# Smart_energy_meter.net
KiCad netlist of a schematic drawn in Altium Designer
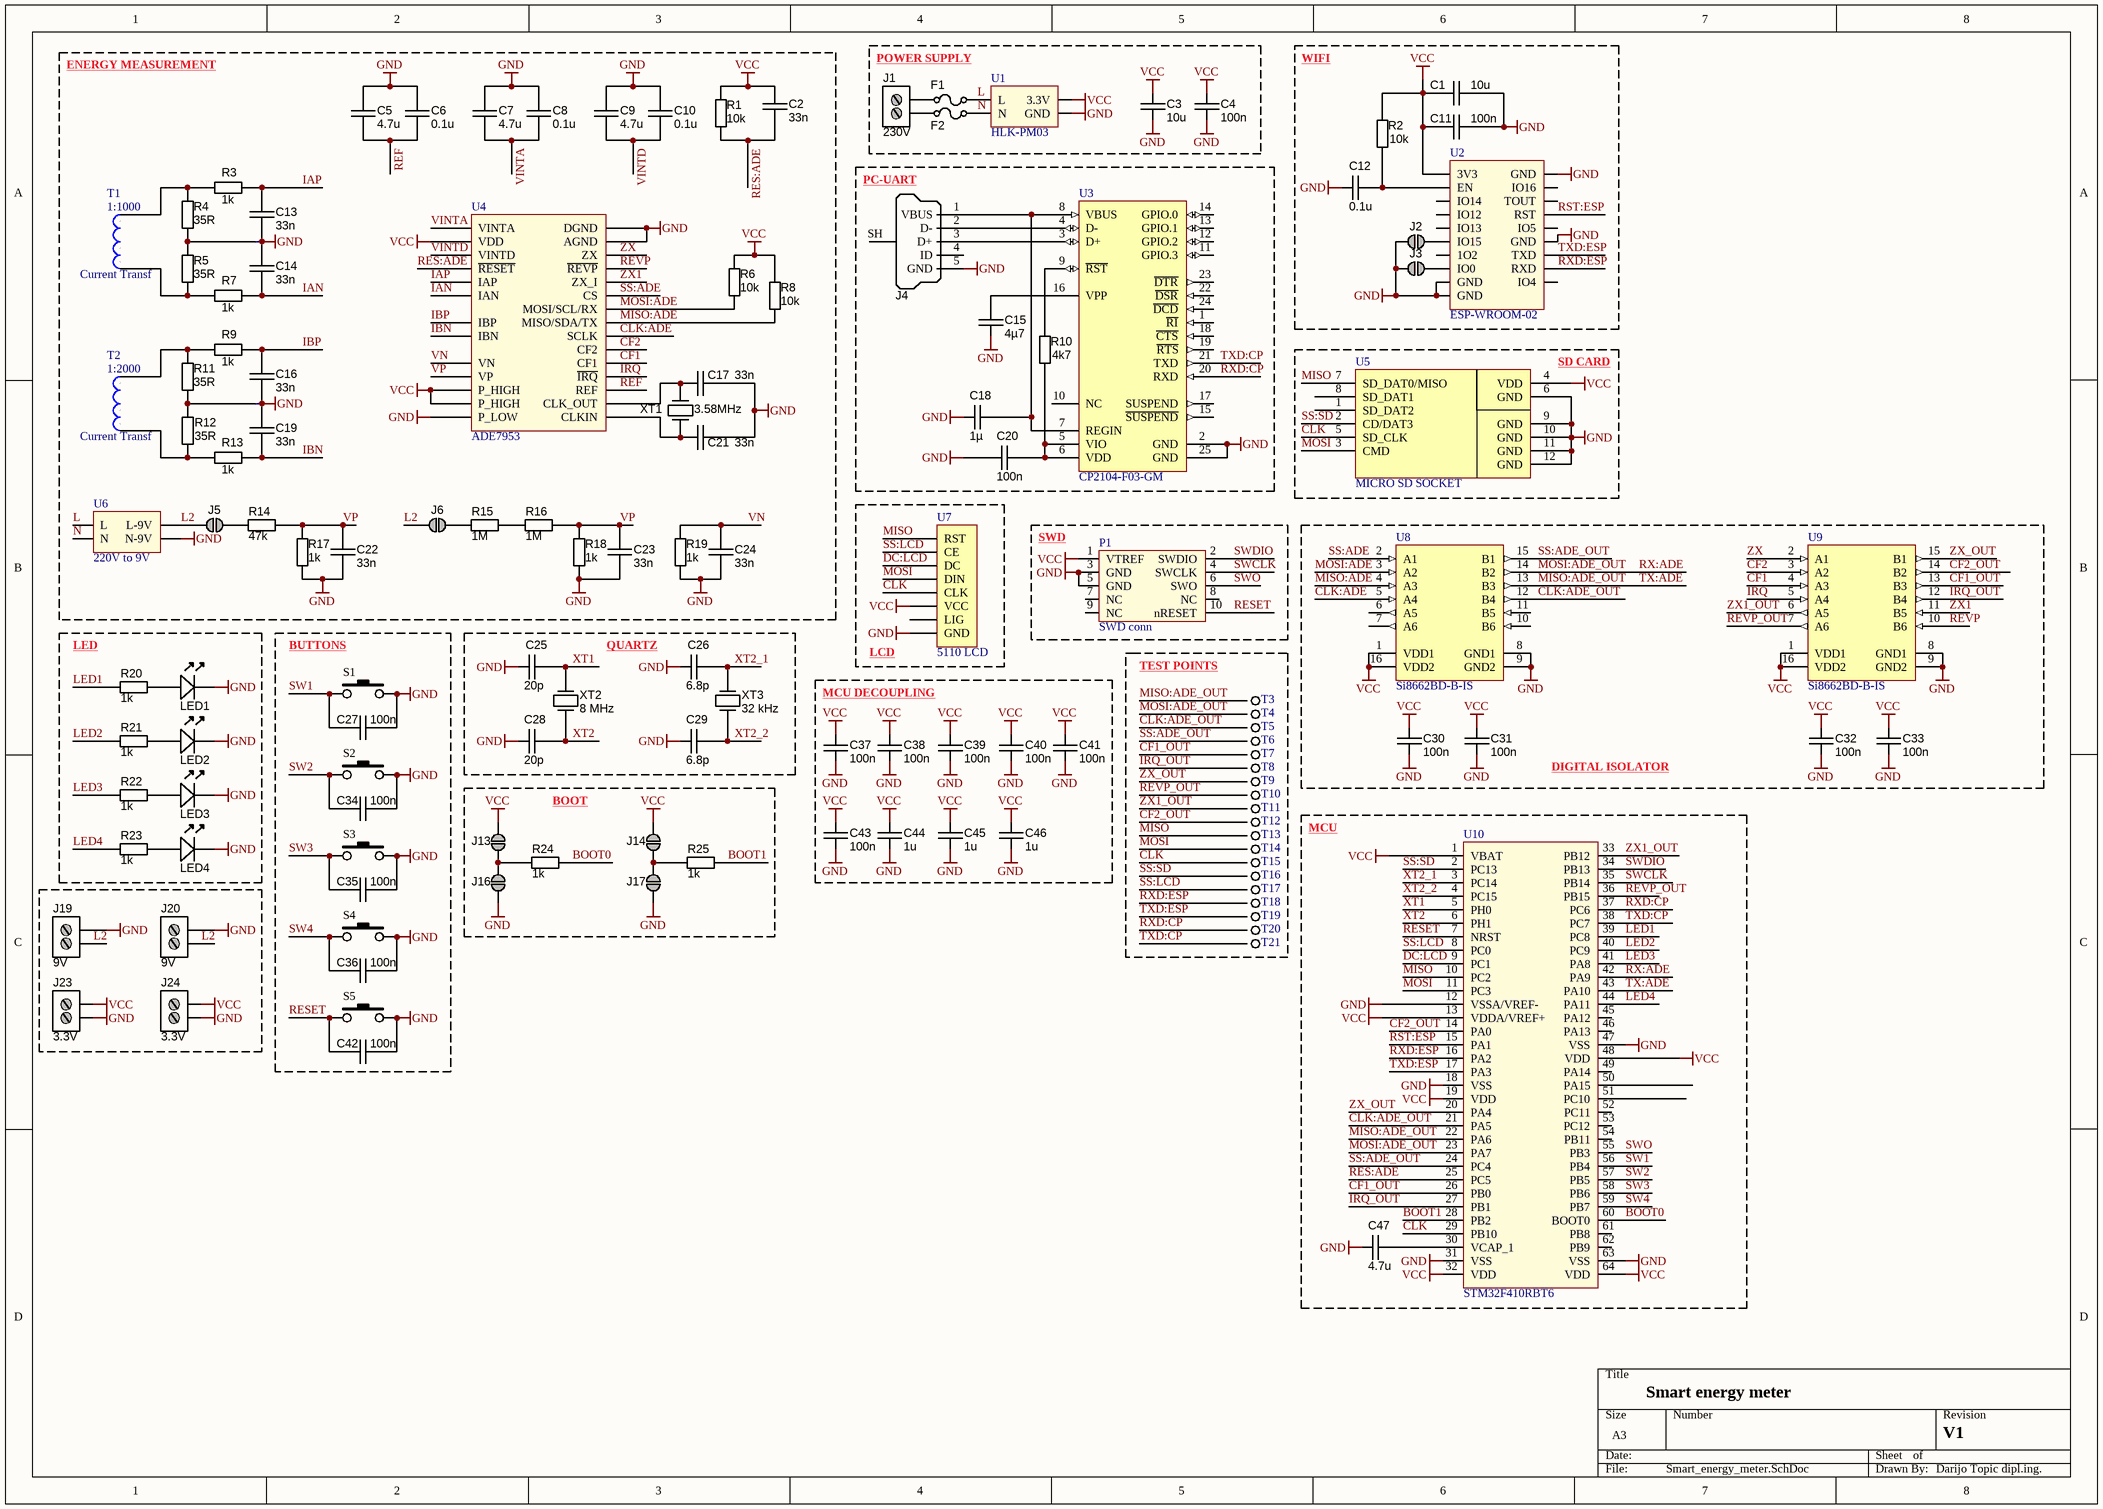
[diagram p0: Smart_energy_meter.SchDoc]

(export (version "E")
  (design (tool "Eeschema 10.0.6"))
  (components
    (comp (ref "C1")
      (value "10u")
      (footprint "CAPC2012X135N")
      (description "Capacitor SMD Cer 100nF 10% 50V X7R 0805")
      (fields (field (name "TOLERANCE") "±10%") (field (name "Comment") "approved sub OK"))
      (libsource (lib "PBL - Capacitors") (part "CAPC_100n_0805_X7R_50V_10%"))
    )
    (comp (ref "C2")
      (value "33n")
      (footprint "CAPC2012X135N")
      (description "Capacitor SMD Cer 100nF 10% 50V X7R 0805")
      (fields (field (name "TOLERANCE") "±10%") (field (name "Comment") "approved sub OK"))
      (libsource (lib "PBL - Capacitors") (part "CAPC_100n_0805_X7R_50V_10%"))
    )
    (comp (ref "C3")
      (value "10u")
      (footprint "CAPC2012X135N")
      (description "Capacitor SMD Cer 100nF 10% 50V X7R 0805")
      (fields (field (name "TOLERANCE") "±10%") (field (name "Comment") "approved sub OK"))
      (libsource (lib "PBL - Capacitors") (part "CAPC_100n_0805_X7R_50V_10%"))
    )
    (comp (ref "C4")
      (value "100n")
      (footprint "CAPC2012X135N")
      (description "Capacitor SMD Cer 100nF 10% 50V X7R 0805")
      (fields (field (name "TOLERANCE") "±10%") (field (name "Comment") "approved sub OK"))
      (libsource (lib "PBL - Capacitors") (part "CAPC_100n_0805_X7R_50V_10%"))
    )
    (comp (ref "C5")
      (value "4.7u")
      (footprint "CAPC2012X135N")
      (description "Capacitor SMD Cer 100nF 10% 50V X7R 0805")
      (fields (field (name "TOLERANCE") "±10%") (field (name "Comment") "approved sub OK"))
      (libsource (lib "PBL - Capacitors") (part "CAPC_100n_0805_X7R_50V_10%"))
    )
    (comp (ref "C6")
      (value "0.1u")
      (footprint "CAPC2012X135N")
      (description "Capacitor SMD Cer 100nF 10% 50V X7R 0805")
      (fields (field (name "TOLERANCE") "±10%") (field (name "Comment") "approved sub OK"))
      (libsource (lib "PBL - Capacitors") (part "CAPC_100n_0805_X7R_50V_10%"))
    )
    (comp (ref "C7")
      (value "4.7u")
      (footprint "CAPC2012X135N")
      (description "Capacitor SMD Cer 100nF 10% 50V X7R 0805")
      (fields (field (name "TOLERANCE") "±10%") (field (name "Comment") "approved sub OK"))
      (libsource (lib "PBL - Capacitors") (part "CAPC_100n_0805_X7R_50V_10%"))
    )
    (comp (ref "C8")
      (value "0.1u")
      (footprint "CAPC2012X135N")
      (description "Capacitor SMD Cer 100nF 10% 50V X7R 0805")
      (fields (field (name "TOLERANCE") "±10%") (field (name "Comment") "approved sub OK"))
      (libsource (lib "PBL - Capacitors") (part "CAPC_100n_0805_X7R_50V_10%"))
    )
    (comp (ref "C9")
      (value "4.7u")
      (footprint "CAPC2012X135N")
      (description "Capacitor SMD Cer 100nF 10% 50V X7R 0805")
      (fields (field (name "TOLERANCE") "±10%") (field (name "Comment") "approved sub OK"))
      (libsource (lib "PBL - Capacitors") (part "CAPC_100n_0805_X7R_50V_10%"))
    )
    (comp (ref "C10")
      (value "0.1u")
      (footprint "CAPC2012X135N")
      (description "Capacitor SMD Cer 100nF 10% 50V X7R 0805")
      (fields (field (name "TOLERANCE") "±10%") (field (name "Comment") "approved sub OK"))
      (libsource (lib "PBL - Capacitors") (part "CAPC_100n_0805_X7R_50V_10%"))
    )
    (comp (ref "C11")
      (value "100n")
      (footprint "CAPC2012X135N")
      (description "Capacitor SMD Cer 100nF 10% 50V X7R 0805")
      (fields (field (name "TOLERANCE") "±10%") (field (name "Comment") "approved sub OK"))
      (libsource (lib "PBL - Capacitors") (part "CAPC_100n_0805_X7R_50V_10%"))
    )
    (comp (ref "C12")
      (value "0.1u")
      (footprint "CAPC2012X135N")
      (description "Capacitor SMD Cer 100nF 10% 50V X7R 0805")
      (fields (field (name "TOLERANCE") "±10%") (field (name "Comment") "approved sub OK"))
      (libsource (lib "PBL - Capacitors") (part "CAPC_100n_0805_X7R_50V_10%"))
    )
    (comp (ref "C13")
      (value "33n")
      (footprint "CAPC2012X135N")
      (description "Capacitor SMD Cer 100nF 10% 50V X7R 0805")
      (fields (field (name "TOLERANCE") "±10%") (field (name "Comment") "approved sub OK"))
      (libsource (lib "PBL - Capacitors") (part "CAPC_100n_0805_X7R_50V_10%"))
    )
    (comp (ref "C14")
      (value "33n")
      (footprint "CAPC2012X135N")
      (description "Capacitor SMD Cer 100nF 10% 50V X7R 0805")
      (fields (field (name "TOLERANCE") "±10%") (field (name "Comment") "approved sub OK"))
      (libsource (lib "PBL - Capacitors") (part "CAPC_100n_0805_X7R_50V_10%"))
    )
    (comp (ref "C15")
      (value "4µ7")
      (footprint "CAPC2012X135N")
      (description "Capacitor SMD Cer 4.7uF 10% 16V X5R 0805")
      (fields (field (name "TOLERANCE") "±10%") (field (name "Comment") "approved sub OK"))
      (libsource (lib "PBL - Capacitors") (part "CAPC_4u7_0805"))
    )
    (comp (ref "C16")
      (value "33n")
      (footprint "CAPC2012X135N")
      (description "Capacitor SMD Cer 100nF 10% 50V X7R 0805")
      (fields (field (name "TOLERANCE") "±10%") (field (name "Comment") "approved sub OK"))
      (libsource (lib "PBL - Capacitors") (part "CAPC_100n_0805_X7R_50V_10%"))
    )
    (comp (ref "C17")
      (value "33n")
      (footprint "CAPC2012X135N")
      (description "Capacitor SMD Cer 100nF 10% 50V X7R 0805")
      (fields (field (name "TOLERANCE") "±10%") (field (name "Comment") "approved sub OK"))
      (libsource (lib "PBL - Capacitors") (part "CAPC_100n_0805_X7R_50V_10%"))
    )
    (comp (ref "C18")
      (value "1µ")
      (footprint "CAPC2012X135N")
      (description "Capacitor SMD Cer 1uF 10% 16V X7R 0805")
      (fields (field (name "TOLERANCE") "±10%") (field (name "Comment") "approved sub OK"))
      (libsource (lib "PBL - Capacitors") (part "CAPC_1u_0805_X7R_16V_10%"))
    )
    (comp (ref "C19")
      (value "33n")
      (footprint "CAPC2012X135N")
      (description "Capacitor SMD Cer 100nF 10% 50V X7R 0805")
      (fields (field (name "TOLERANCE") "±10%") (field (name "Comment") "approved sub OK"))
      (libsource (lib "PBL - Capacitors") (part "CAPC_100n_0805_X7R_50V_10%"))
    )
    (comp (ref "C20")
      (value "100n")
      (footprint "CAPC2012X135N")
      (description "Capacitor SMD Cer 100nF 10% 50V X7R 0805")
      (fields (field (name "TOLERANCE") "±10%") (field (name "Comment") "approved sub OK"))
      (libsource (lib "PBL - Capacitors") (part "CAPC_100n_0805_X7R_50V_10%"))
    )
    (comp (ref "C21")
      (value "33n")
      (footprint "CAPC2012X135N")
      (description "Capacitor SMD Cer 100nF 10% 50V X7R 0805")
      (fields (field (name "TOLERANCE") "±10%") (field (name "Comment") "approved sub OK"))
      (libsource (lib "PBL - Capacitors") (part "CAPC_100n_0805_X7R_50V_10%"))
    )
    (comp (ref "C22")
      (value "33n")
      (footprint "CAPC2012X135N")
      (description "Capacitor SMD Cer 100nF 10% 50V X7R 0805")
      (fields (field (name "TOLERANCE") "±10%") (field (name "Comment") "approved sub OK"))
      (libsource (lib "PBL - Capacitors") (part "CAPC_100n_0805_X7R_50V_10%"))
    )
    (comp (ref "C23")
      (value "33n")
      (footprint "CAPC2012X135N")
      (description "Capacitor SMD Cer 100nF 10% 50V X7R 0805")
      (fields (field (name "TOLERANCE") "±10%") (field (name "Comment") "approved sub OK"))
      (libsource (lib "PBL - Capacitors") (part "CAPC_100n_0805_X7R_50V_10%"))
    )
    (comp (ref "C24")
      (value "33n")
      (footprint "CAPC2012X135N")
      (description "Capacitor SMD Cer 100nF 10% 50V X7R 0805")
      (fields (field (name "TOLERANCE") "±10%") (field (name "Comment") "approved sub OK"))
      (libsource (lib "PBL - Capacitors") (part "CAPC_100n_0805_X7R_50V_10%"))
    )
    (comp (ref "C25")
      (value "20p")
      (footprint "CAPC2012X135N")
      (description "Capacitor SMD Cer 100nF 10% 50V X7R 0805")
      (fields (field (name "TOLERANCE") "±10%") (field (name "Comment") "approved sub OK"))
      (libsource (lib "PBL - Capacitors") (part "CAPC_100n_0805_X7R_50V_10%"))
    )
    (comp (ref "C26")
      (value "6.8p")
      (footprint "CAPC2012X135N")
      (description "Capacitor SMD Cer 100nF 10% 50V X7R 0805")
      (fields (field (name "TOLERANCE") "±10%") (field (name "Comment") "approved sub OK"))
      (libsource (lib "PBL - Capacitors") (part "CAPC_100n_0805_X7R_50V_10%"))
    )
    (comp (ref "C27")
      (value "100n")
      (footprint "CAPC2012X135N")
      (description "Capacitor SMD Cer 100nF 10% 50V X7R 0805")
      (fields (field (name "TOLERANCE") "±10%") (field (name "Comment") "approved sub OK"))
      (libsource (lib "PBL - Capacitors") (part "CAPC_100n_0805_X7R_50V_10%"))
    )
    (comp (ref "C28")
      (value "20p")
      (footprint "CAPC2012X135N")
      (description "Capacitor SMD Cer 100nF 10% 50V X7R 0805")
      (fields (field (name "TOLERANCE") "±10%") (field (name "Comment") "approved sub OK"))
      (libsource (lib "PBL - Capacitors") (part "CAPC_100n_0805_X7R_50V_10%"))
    )
    (comp (ref "C29")
      (value "6.8p")
      (footprint "CAPC2012X135N")
      (description "Capacitor SMD Cer 100nF 10% 50V X7R 0805")
      (fields (field (name "TOLERANCE") "±10%") (field (name "Comment") "approved sub OK"))
      (libsource (lib "PBL - Capacitors") (part "CAPC_100n_0805_X7R_50V_10%"))
    )
    (comp (ref "C30")
      (value "100n")
      (footprint "CAPC2012X135N")
      (description "Capacitor SMD Cer 100nF 10% 50V X7R 0805")
      (fields (field (name "TOLERANCE") "±10%") (field (name "Comment") "approved sub OK"))
      (libsource (lib "PBL - Capacitors") (part "CAPC_100n_0805_X7R_50V_10%"))
    )
    (comp (ref "C31")
      (value "100n")
      (footprint "CAPC2012X135N")
      (description "Capacitor SMD Cer 100nF 10% 50V X7R 0805")
      (fields (field (name "TOLERANCE") "±10%") (field (name "Comment") "approved sub OK"))
      (libsource (lib "PBL - Capacitors") (part "CAPC_100n_0805_X7R_50V_10%"))
    )
    (comp (ref "C32")
      (value "100n")
      (footprint "CAPC2012X135N")
      (description "Capacitor SMD Cer 100nF 10% 50V X7R 0805")
      (fields (field (name "TOLERANCE") "±10%") (field (name "Comment") "approved sub OK"))
      (libsource (lib "PBL - Capacitors") (part "CAPC_100n_0805_X7R_50V_10%"))
    )
    (comp (ref "C33")
      (value "100n")
      (footprint "CAPC2012X135N")
      (description "Capacitor SMD Cer 100nF 10% 50V X7R 0805")
      (fields (field (name "TOLERANCE") "±10%") (field (name "Comment") "approved sub OK"))
      (libsource (lib "PBL - Capacitors") (part "CAPC_100n_0805_X7R_50V_10%"))
    )
    (comp (ref "C34")
      (value "100n")
      (footprint "CAPC2012X135N")
      (description "Capacitor SMD Cer 100nF 10% 50V X7R 0805")
      (fields (field (name "TOLERANCE") "±10%") (field (name "Comment") "approved sub OK"))
      (libsource (lib "PBL - Capacitors") (part "CAPC_100n_0805_X7R_50V_10%"))
    )
    (comp (ref "C35")
      (value "100n")
      (footprint "CAPC2012X135N")
      (description "Capacitor SMD Cer 100nF 10% 50V X7R 0805")
      (fields (field (name "TOLERANCE") "±10%") (field (name "Comment") "approved sub OK"))
      (libsource (lib "PBL - Capacitors") (part "CAPC_100n_0805_X7R_50V_10%"))
    )
    (comp (ref "C36")
      (value "100n")
      (footprint "CAPC2012X135N")
      (description "Capacitor SMD Cer 100nF 10% 50V X7R 0805")
      (fields (field (name "TOLERANCE") "±10%") (field (name "Comment") "approved sub OK"))
      (libsource (lib "PBL - Capacitors") (part "CAPC_100n_0805_X7R_50V_10%"))
    )
    (comp (ref "C37")
      (value "100n")
      (footprint "CAPC2012X135N")
      (description "Capacitor SMD Cer 100nF 10% 50V X7R 0805")
      (fields (field (name "TOLERANCE") "±10%") (field (name "Comment") "approved sub OK"))
      (libsource (lib "PBL - Capacitors") (part "CAPC_100n_0805_X7R_50V_10%"))
    )
    (comp (ref "C38")
      (value "100n")
      (footprint "CAPC2012X135N")
      (description "Capacitor SMD Cer 100nF 10% 50V X7R 0805")
      (fields (field (name "TOLERANCE") "±10%") (field (name "Comment") "approved sub OK"))
      (libsource (lib "PBL - Capacitors") (part "CAPC_100n_0805_X7R_50V_10%"))
    )
    (comp (ref "C39")
      (value "100n")
      (footprint "CAPC2012X135N")
      (description "Capacitor SMD Cer 100nF 10% 50V X7R 0805")
      (fields (field (name "TOLERANCE") "±10%") (field (name "Comment") "approved sub OK"))
      (libsource (lib "PBL - Capacitors") (part "CAPC_100n_0805_X7R_50V_10%"))
    )
    (comp (ref "C40")
      (value "100n")
      (footprint "CAPC2012X135N")
      (description "Capacitor SMD Cer 100nF 10% 50V X7R 0805")
      (fields (field (name "TOLERANCE") "±10%") (field (name "Comment") "approved sub OK"))
      (libsource (lib "PBL - Capacitors") (part "CAPC_100n_0805_X7R_50V_10%"))
    )
    (comp (ref "C41")
      (value "100n")
      (footprint "CAPC2012X135N")
      (description "Capacitor SMD Cer 100nF 10% 50V X7R 0805")
      (fields (field (name "TOLERANCE") "±10%") (field (name "Comment") "approved sub OK"))
      (libsource (lib "PBL - Capacitors") (part "CAPC_100n_0805_X7R_50V_10%"))
    )
    (comp (ref "C42")
      (value "100n")
      (footprint "CAPC2012X135N")
      (description "Capacitor SMD Cer 100nF 10% 50V X7R 0805")
      (fields (field (name "TOLERANCE") "±10%") (field (name "Comment") "approved sub OK"))
      (libsource (lib "PBL - Capacitors") (part "CAPC_100n_0805_X7R_50V_10%"))
    )
    (comp (ref "C43")
      (value "100n")
      (footprint "CAPC2012X135N")
      (description "Capacitor SMD Cer 100nF 10% 50V X7R 0805")
      (fields (field (name "TOLERANCE") "±10%") (field (name "Comment") "approved sub OK"))
      (libsource (lib "PBL - Capacitors") (part "CAPC_100n_0805_X7R_50V_10%"))
    )
    (comp (ref "C44")
      (value "1u")
      (footprint "CAPC2012X135N")
      (description "Capacitor SMD Cer 100nF 10% 50V X7R 0805")
      (fields (field (name "TOLERANCE") "±10%") (field (name "Comment") "approved sub OK"))
      (libsource (lib "PBL - Capacitors") (part "CAPC_100n_0805_X7R_50V_10%"))
    )
    (comp (ref "C45")
      (value "1u")
      (footprint "CAPC2012X135N")
      (description "Capacitor SMD Cer 100nF 10% 50V X7R 0805")
      (fields (field (name "TOLERANCE") "±10%") (field (name "Comment") "approved sub OK"))
      (libsource (lib "PBL - Capacitors") (part "CAPC_100n_0805_X7R_50V_10%"))
    )
    (comp (ref "C46")
      (value "1u")
      (footprint "CAPC2012X135N")
      (description "Capacitor SMD Cer 100nF 10% 50V X7R 0805")
      (fields (field (name "TOLERANCE") "±10%") (field (name "Comment") "approved sub OK"))
      (libsource (lib "PBL - Capacitors") (part "CAPC_100n_0805_X7R_50V_10%"))
    )
    (comp (ref "C47")
      (value "4.7u")
      (footprint "CAPC2012X135N")
      (description "Capacitor SMD Cer 100nF 10% 50V X7R 0805")
      (fields (field (name "TOLERANCE") "±10%") (field (name "Comment") "approved sub OK"))
      (libsource (lib "PBL - Capacitors") (part "CAPC_100n_0805_X7R_50V_10%"))
    )
    (comp (ref "F1")
      (value "Slow-blow")
      (footprint "Fuses 20A 250VAC")
      (description "Fuse 160mA 63VDC 0603 SMD")
      (libsource (lib "PBL - Fuses and Protection") (part "FUSE_160mA_0603"))
    )
    (comp (ref "F2")
      (value "Slow-blow")
      (footprint "Fuses 20A 250VAC")
      (description "Fuse 160mA 63VDC 0603 SMD")
      (libsource (lib "PBL - Fuses and Protection") (part "FUSE_160mA_0603"))
    )
    (comp (ref "J1")
      (value "230V")
      (footprint "2P_PCB_ScrewTerm_90S_3.81MM")
      (description "Terminal Block Screw Type THT 2-Position 3.81mm pitch")
      (libsource (lib "PBL - Connectors") (part "2P_ScrewTerm_90S_3.81MM"))
    )
    (comp (ref "J2")
      (value "Jumper")
      (footprint "HDR1X2")
      (description "SMD jumper")
      (libsource (lib "PBL - Pads and Jumpers") (part "JUMP1"))
    )
    (comp (ref "J3")
      (value "Jumper")
      (footprint "HDR1X2")
      (description "SMD jumper")
      (libsource (lib "PBL - Pads and Jumpers") (part "JUMP1"))
    )
    (comp (ref "J4")
      (value "USB Micro Type B (recommended if hand soldering)")
      (footprint "PBL - SMD Packages:USB_Micro-B_FCI_SMD")
      (description "Connector SMD-THD USB Micro Type B middle mount")
      (libsource (lib "PBL - Connectors") (part "USB_Micro_TypeB_FCI"))
    )
    (comp (ref "J5")
      (value "Jumper")
      (footprint "HDR1X2")
      (description "SMD jumper")
      (libsource (lib "PBL - Pads and Jumpers") (part "JUMP1"))
    )
    (comp (ref "J6")
      (value "Jumper")
      (footprint "HDR1X2")
      (description "SMD jumper")
      (libsource (lib "PBL - Pads and Jumpers") (part "JUMP1"))
    )
    (comp (ref "J13")
      (value "Jumper")
      (footprint "HDR1X2")
      (description "SMD jumper")
      (libsource (lib "PBL - Pads and Jumpers") (part "JUMP1"))
    )
    (comp (ref "J14")
      (value "Jumper")
      (footprint "HDR1X2")
      (description "SMD jumper")
      (libsource (lib "PBL - Pads and Jumpers") (part "JUMP1"))
    )
    (comp (ref "J16")
      (value "Jumper")
      (footprint "HDR1X2")
      (description "SMD jumper")
      (libsource (lib "PBL - Pads and Jumpers") (part "JUMP1"))
    )
    (comp (ref "J17")
      (value "Jumper")
      (footprint "HDR1X2")
      (description "SMD jumper")
      (libsource (lib "PBL - Pads and Jumpers") (part "JUMP1"))
    )
    (comp (ref "J19")
      (value "9V")
      (footprint "2P_PCB_ScrewTerm_90S_3.81MM")
      (description "Terminal Block Screw Type THT 2-Position 3.81mm pitch")
      (libsource (lib "PBL - Connectors") (part "2P_ScrewTerm_90S_3.81MM"))
    )
    (comp (ref "J20")
      (value "9V")
      (footprint "2P_PCB_ScrewTerm_90S_3.81MM")
      (description "Terminal Block Screw Type THT 2-Position 3.81mm pitch")
      (libsource (lib "PBL - Connectors") (part "2P_ScrewTerm_90S_3.81MM"))
    )
    (comp (ref "J23")
      (value "3.3V")
      (footprint "2P_PCB_ScrewTerm_90S_3.81MM")
      (description "Terminal Block Screw Type THT 2-Position 3.81mm pitch")
      (libsource (lib "PBL - Connectors") (part "2P_ScrewTerm_90S_3.81MM"))
    )
    (comp (ref "J24")
      (value "3.3V")
      (footprint "2P_PCB_ScrewTerm_90S_3.81MM")
      (description "Terminal Block Screw Type THT 2-Position 3.81mm pitch")
      (libsource (lib "PBL - Connectors") (part "2P_ScrewTerm_90S_3.81MM"))
    )
    (comp (ref "LED1")
      (value "~")
      (footprint "LED-0805-K")
      (description "LED, 0805 SMD, Green")
      (libsource (lib "PBL - Light Sources") (part "LED_SMD_Green_0805_6mcd"))
    )
    (comp (ref "LED2")
      (value "~")
      (footprint "LED-0805-K")
      (description "LED, 0805 SMD, Green")
      (libsource (lib "PBL - Light Sources") (part "LED_SMD_Green_0805_6mcd"))
    )
    (comp (ref "LED3")
      (value "~")
      (footprint "LED-0805-K")
      (description "LED, 0805 SMD, Green")
      (libsource (lib "PBL - Light Sources") (part "LED_SMD_Green_0805_6mcd"))
    )
    (comp (ref "LED4")
      (value "~")
      (footprint "LED-0805-K")
      (description "LED, 0805 SMD, Green")
      (libsource (lib "PBL - Light Sources") (part "LED_SMD_Green_0805_6mcd"))
    )
    (comp (ref "P1")
      (value "SWD conn")
      (footprint "HDR2X5_CEN")
      (description "SWD connector")
      (libsource (lib "Lib_darijo") (part "SW_debug"))
    )
    (comp (ref "R1")
      (value "10k")
      (footprint "RESC2012X70N")
      (description "Resistor SMD chip 4.7k Ohm 0.125W 1% 0805")
      (fields (field (name "TOLERANCE") "±1%") (field (name "Comment") "Thick Film"))
      (libsource (lib "PBL - Resistors") (part "RES_4K7_0805_1%"))
    )
    (comp (ref "R2")
      (value "10k")
      (footprint "RESC2012X70N")
      (description "Resistor SMD chip 4.7k Ohm 0.125W 1% 0805")
      (fields (field (name "TOLERANCE") "±1%") (field (name "Comment") "Thick Film"))
      (libsource (lib "") (part "RES_4K7_0805_1%_1"))
    )
    (comp (ref "R3")
      (value "1k")
      (footprint "RESC2012X70N")
      (description "Resistor SMD chip 4.7k Ohm 0.125W 1% 0805")
      (fields (field (name "TOLERANCE") "±1%") (field (name "Comment") "Thick Film"))
      (libsource (lib "") (part "RES_4K7_0805_1%_2"))
    )
    (comp (ref "R4")
      (value "35R")
      (footprint "RESC2012X70N")
      (description "Resistor SMD chip 4.7k Ohm 0.125W 1% 0805")
      (fields (field (name "TOLERANCE") "±1%") (field (name "Comment") "Thick Film"))
      (libsource (lib "PBL - Resistors") (part "RES_4K7_0805_1%"))
    )
    (comp (ref "R5")
      (value "35R")
      (footprint "RESC2012X70N")
      (description "Resistor SMD chip 4.7k Ohm 0.125W 1% 0805")
      (fields (field (name "TOLERANCE") "±1%") (field (name "Comment") "Thick Film"))
      (libsource (lib "PBL - Resistors") (part "RES_4K7_0805_1%"))
    )
    (comp (ref "R6")
      (value "10k")
      (footprint "RESC2012X70N")
      (description "Resistor SMD chip 4.7k Ohm 0.125W 1% 0805")
      (fields (field (name "TOLERANCE") "±1%") (field (name "Comment") "Thick Film"))
      (libsource (lib "PBL - Resistors") (part "RES_4K7_0805_1%"))
    )
    (comp (ref "R7")
      (value "1k")
      (footprint "RESC2012X70N")
      (description "Resistor SMD chip 4.7k Ohm 0.125W 1% 0805")
      (fields (field (name "TOLERANCE") "±1%") (field (name "Comment") "Thick Film"))
      (libsource (lib "") (part "RES_4K7_0805_1%_2"))
    )
    (comp (ref "R8")
      (value "10k")
      (footprint "RESC2012X70N")
      (description "Resistor SMD chip 4.7k Ohm 0.125W 1% 0805")
      (fields (field (name "TOLERANCE") "±1%") (field (name "Comment") "Thick Film"))
      (libsource (lib "PBL - Resistors") (part "RES_4K7_0805_1%"))
    )
    (comp (ref "R9")
      (value "1k")
      (footprint "RESC2012X70N")
      (description "Resistor SMD chip 4.7k Ohm 0.125W 1% 0805")
      (fields (field (name "TOLERANCE") "±1%") (field (name "Comment") "Thick Film"))
      (libsource (lib "") (part "RES_4K7_0805_1%_2"))
    )
    (comp (ref "R10")
      (value "4k7")
      (footprint "RESC2012X70N")
      (description "Resistor SMD chip 4.7k Ohm 0.125W 1% 0805")
      (fields (field (name "TOLERANCE") "±1%") (field (name "Comment") "Thick Film"))
      (libsource (lib "") (part "RES_4K7_0805_1%_1"))
    )
    (comp (ref "R11")
      (value "35R")
      (footprint "RESC2012X70N")
      (description "Resistor SMD chip 4.7k Ohm 0.125W 1% 0805")
      (fields (field (name "TOLERANCE") "±1%") (field (name "Comment") "Thick Film"))
      (libsource (lib "PBL - Resistors") (part "RES_4K7_0805_1%"))
    )
    (comp (ref "R12")
      (value "35R")
      (footprint "RESC2012X70N")
      (description "Resistor SMD chip 4.7k Ohm 0.125W 1% 0805")
      (fields (field (name "TOLERANCE") "±1%") (field (name "Comment") "Thick Film"))
      (libsource (lib "PBL - Resistors") (part "RES_4K7_0805_1%"))
    )
    (comp (ref "R13")
      (value "1k")
      (footprint "RESC2012X70N")
      (description "Resistor SMD chip 4.7k Ohm 0.125W 1% 0805")
      (fields (field (name "TOLERANCE") "±1%") (field (name "Comment") "Thick Film"))
      (libsource (lib "") (part "RES_4K7_0805_1%_2"))
    )
    (comp (ref "R14")
      (value "47k")
      (footprint "RESC2012X70N")
      (description "Resistor SMD chip 4.7k Ohm 0.125W 1% 0805")
      (fields (field (name "TOLERANCE") "±1%") (field (name "Comment") "Thick Film"))
      (libsource (lib "") (part "RES_4K7_0805_1%_2"))
    )
    (comp (ref "R15")
      (value "1M")
      (footprint "RESC2012X70N")
      (description "Resistor SMD chip 4.7k Ohm 0.125W 1% 0805")
      (fields (field (name "TOLERANCE") "±1%") (field (name "Comment") "Thick Film"))
      (libsource (lib "") (part "RES_4K7_0805_1%_3"))
    )
    (comp (ref "R16")
      (value "1M")
      (footprint "RESC2012X70N")
      (description "Resistor SMD chip 4.7k Ohm 0.125W 1% 0805")
      (fields (field (name "TOLERANCE") "±1%") (field (name "Comment") "Thick Film"))
      (libsource (lib "") (part "RES_4K7_0805_1%_3"))
    )
    (comp (ref "R17")
      (value "1k")
      (footprint "RESC2012X70N")
      (description "Resistor SMD chip 4.7k Ohm 0.125W 1% 0805")
      (fields (field (name "TOLERANCE") "±1%") (field (name "Comment") "Thick Film"))
      (libsource (lib "PBL - Resistors") (part "RES_4K7_0805_1%"))
    )
    (comp (ref "R18")
      (value "1k")
      (footprint "RESC2012X70N")
      (description "Resistor SMD chip 4.7k Ohm 0.125W 1% 0805")
      (fields (field (name "TOLERANCE") "±1%") (field (name "Comment") "Thick Film"))
      (libsource (lib "PBL - Resistors") (part "RES_4K7_0805_1%"))
    )
    (comp (ref "R19")
      (value "1k")
      (footprint "RESC2012X70N")
      (description "Resistor SMD chip 4.7k Ohm 0.125W 1% 0805")
      (fields (field (name "TOLERANCE") "±1%") (field (name "Comment") "Thick Film"))
      (libsource (lib "PBL - Resistors") (part "RES_4K7_0805_1%"))
    )
    (comp (ref "R20")
      (value "1k")
      (footprint "RESC2012X70N")
      (description "Resistor SMD chip 4.7k Ohm 0.125W 1% 0805")
      (fields (field (name "TOLERANCE") "±1%") (field (name "Comment") "Thick Film"))
      (libsource (lib "") (part "RES_4K7_0805_1%_2"))
    )
    (comp (ref "R21")
      (value "1k")
      (footprint "RESC2012X70N")
      (description "Resistor SMD chip 4.7k Ohm 0.125W 1% 0805")
      (fields (field (name "TOLERANCE") "±1%") (field (name "Comment") "Thick Film"))
      (libsource (lib "") (part "RES_4K7_0805_1%_2"))
    )
    (comp (ref "R22")
      (value "1k")
      (footprint "RESC2012X70N")
      (description "Resistor SMD chip 4.7k Ohm 0.125W 1% 0805")
      (fields (field (name "TOLERANCE") "±1%") (field (name "Comment") "Thick Film"))
      (libsource (lib "") (part "RES_4K7_0805_1%_2"))
    )
    (comp (ref "R23")
      (value "1k")
      (footprint "RESC2012X70N")
      (description "Resistor SMD chip 4.7k Ohm 0.125W 1% 0805")
      (fields (field (name "TOLERANCE") "±1%") (field (name "Comment") "Thick Film"))
      (libsource (lib "") (part "RES_4K7_0805_1%_2"))
    )
    (comp (ref "R24")
      (value "1k")
      (footprint "RESC2012X70N")
      (description "Resistor SMD chip 4.7k Ohm 0.125W 1% 0805")
      (fields (field (name "TOLERANCE") "±1%") (field (name "Comment") "Thick Film"))
      (libsource (lib "") (part "RES_4K7_0805_1%_2"))
    )
    (comp (ref "R25")
      (value "1k")
      (footprint "RESC2012X70N")
      (description "Resistor SMD chip 4.7k Ohm 0.125W 1% 0805")
      (fields (field (name "TOLERANCE") "±1%") (field (name "Comment") "Thick Film"))
      (libsource (lib "") (part "RES_4K7_0805_1%_2"))
    )
    (comp (ref "S1")
      (value "SMD_BUTTON")
      (footprint "SMD_BUTTON")
      (libsource (lib "Lib_darijo") (part "SMD_BUTTON"))
    )
    (comp (ref "S2")
      (value "SMD_BUTTON")
      (footprint "SMD_BUTTON")
      (libsource (lib "Lib_darijo") (part "SMD_BUTTON"))
    )
    (comp (ref "S3")
      (value "SMD_BUTTON")
      (footprint "SMD_BUTTON")
      (libsource (lib "Lib_darijo") (part "SMD_BUTTON"))
    )
    (comp (ref "S4")
      (value "SMD_BUTTON")
      (footprint "SMD_BUTTON")
      (libsource (lib "Lib_darijo") (part "SMD_BUTTON"))
    )
    (comp (ref "S5")
      (value "SMD_BUTTON")
      (footprint "SMD_BUTTON")
      (libsource (lib "Lib_darijo") (part "SMD_BUTTON"))
    )
    (comp (ref "T1")
      (value "Current Transf")
      (footprint "lib_darijo:CST-1025")
      (description "Current Transformer")
      (fields (field (name "RATIO") "1:1000"))
      (libsource (lib "Schlib1") (part "Transf_Current"))
    )
    (comp (ref "T2")
      (value "Current Transf")
      (footprint "DL-CT1005A")
      (description "Current Transformer")
      (fields (field (name "RATIO") "1:2000"))
      (libsource (lib "Schlib1") (part "Transf_Current"))
    )
    (comp (ref "T3")
      (value "Test Point")
      (footprint "PIN1")
      (libsource (lib "Lib_darijo") (part "Test_Point"))
    )
    (comp (ref "T4")
      (value "Test Point")
      (footprint "PIN1")
      (libsource (lib "Lib_darijo") (part "Test_Point"))
    )
    (comp (ref "T5")
      (value "Test Point")
      (footprint "PIN1")
      (libsource (lib "Lib_darijo") (part "Test_Point"))
    )
    (comp (ref "T6")
      (value "Test Point")
      (footprint "PIN1")
      (libsource (lib "Lib_darijo") (part "Test_Point"))
    )
    (comp (ref "T7")
      (value "Test Point")
      (footprint "PIN1")
      (libsource (lib "Lib_darijo") (part "Test_Point"))
    )
    (comp (ref "T8")
      (value "Test Point")
      (footprint "PIN1")
      (libsource (lib "Lib_darijo") (part "Test_Point"))
    )
    (comp (ref "T9")
      (value "Test Point")
      (footprint "PIN1")
      (libsource (lib "Lib_darijo") (part "Test_Point"))
    )
    (comp (ref "T10")
      (value "Test Point")
      (footprint "PIN1")
      (libsource (lib "Lib_darijo") (part "Test_Point"))
    )
    (comp (ref "T11")
      (value "Test Point")
      (footprint "PIN1")
      (libsource (lib "Lib_darijo") (part "Test_Point"))
    )
    (comp (ref "T12")
      (value "Test Point")
      (footprint "PIN1")
      (libsource (lib "Lib_darijo") (part "Test_Point"))
    )
    (comp (ref "T13")
      (value "Test Point")
      (footprint "PIN1")
      (libsource (lib "Lib_darijo") (part "Test_Point"))
    )
    (comp (ref "T14")
      (value "Test Point")
      (footprint "PIN1")
      (libsource (lib "Lib_darijo") (part "Test_Point"))
    )
    (comp (ref "T15")
      (value "Test Point")
      (footprint "PIN1")
      (libsource (lib "Lib_darijo") (part "Test_Point"))
    )
    (comp (ref "T16")
      (value "Test Point")
      (footprint "PIN1")
      (libsource (lib "Lib_darijo") (part "Test_Point"))
    )
    (comp (ref "T17")
      (value "Test Point")
      (footprint "PIN1")
      (libsource (lib "Lib_darijo") (part "Test_Point"))
    )
    (comp (ref "T18")
      (value "Test Point")
      (footprint "PIN1")
      (libsource (lib "Lib_darijo") (part "Test_Point"))
    )
    (comp (ref "T19")
      (value "Test Point")
      (footprint "PIN1")
      (libsource (lib "Lib_darijo") (part "Test_Point"))
    )
    (comp (ref "T20")
      (value "Test Point")
      (footprint "PIN1")
      (libsource (lib "Lib_darijo") (part "Test_Point"))
    )
    (comp (ref "T21")
      (value "Test Point")
      (footprint "PIN1")
      (libsource (lib "Lib_darijo") (part "Test_Point"))
    )
    (comp (ref "U1")
      (value "HLK-PM03")
      (footprint "lib_darijo:HLK-PM03")
      (description "AC 220V to DC 3.3V")
      (libsource (lib "Lib_darijo") (part "HLK-PM03"))
    )
    (comp (ref "U2")
      (value "ESP-WROOM-02")
      (footprint "ESP-WROOM-02")
      (description "WIFI module")
      (libsource (lib "Lib_darijo") (part "ESP-WROOM-02"))
    )
    (comp (ref "U3")
      (value "CP2104-F03-GM")
      (footprint "SLAB-QFN-24-2675x2675TP_N")
      (fields (field (name "MANUFACTURER") "Silicon Labs"))
      (libsource (lib "Silicon Labs Interface") (part "CP2104-F03-GM"))
    )
    (comp (ref "U4")
      (value "ADE7953")
      (footprint "CP_28_6")
      (description "Energy meter")
      (libsource (lib "Lib_darijo") (part "ADE7953"))
    )
    (comp (ref "U5")
      (value "MICRO SD SOCKET")
      (footprint "lib_darijo:SDSOCKET_MOLEX")
      (description "uSD SOCKET")
      (fields (field (name "MANUFACTURER") "Molex"))
      (libsource (lib "Lib_darijo") (part "MICRO_SD_MOLEX"))
    )
    (comp (ref "U6")
      (value "220V to 9V")
      (footprint "TRAFO 220-9")
      (description "BV EI 304 2041")
      (libsource (lib "Lib_darijo") (part "TRANSFOR 220V-9V"))
    )
    (comp (ref "U7")
      (value "5110 LCD")
      (footprint "Miscellaneous Connectors:HDR1X8")
      (description "Header, 8-Pin")
      (fields (field (name "PUBLISHER") "Altium Limited"))
      (libsource (lib "Miscellaneous Connectors") (part "Header 8"))
    )
    (comp (ref "U8")
      (value "Si8662BD-B-IS")
      (footprint "SLAB-SOIC-16-WB_N")
      (fields (field (name "MANUFACTURER") "Silicon Labs"))
      (libsource (lib "Silicon Labs Isolation and Power") (part "Si8662BD-B-IS"))
    )
    (comp (ref "U9")
      (value "Si8662BD-B-IS")
      (footprint "SLAB-SOIC-16-WB_N")
      (fields (field (name "MANUFACTURER") "Silicon Labs"))
      (libsource (lib "Silicon Labs Isolation and Power") (part "Si8662BD-B-IS"))
    )
    (comp (ref "U10")
      (value "STM32F410RBT6")
      (footprint "STM-LQFP64_L")
      (description "STM32 Cortex M4 - F4 series")
      (libsource (lib "Lib_darijo") (part "STM32F410CB"))
    )
    (comp (ref "XT1")
      (value "3.58MHz")
      (footprint "CRYSTAL_HC49-US-SM")
      (description "Resonator Ceramic 6.00 MHz 30ppm")
      (libsource (lib "PBL - Resonators") (part "Crystal_6MHz_HC49/US"))
    )
    (comp (ref "XT2")
      (value "8 MHz")
      (footprint "CRYSTAL_HC49-US-SM")
      (description "Resonator Ceramic 6.00 MHz 30ppm")
      (libsource (lib "PBL - Resonators") (part "Crystal_6MHz_HC49/US"))
    )
    (comp (ref "XT3")
      (value "32 kHz")
      (footprint "85SMX")
      (description "Resonator Ceramic 6.00 MHz 30ppm")
      (libsource (lib "PBL - Resonators") (part "Crystal_6MHz_HC49/US"))
    )
  )
  (nets
    (net (code "1") (name "/BOOT0") (class "Default")
      (node (ref "R24") (pin "2") (pinfunction "2_2") (pintype "passive"))
      (node (ref "U10") (pin "60") (pinfunction "BOOT0_60") (pintype "passive"))
    )
    (net (code "2") (name "/BOOT1") (class "Default")
      (node (ref "R25") (pin "2") (pinfunction "2_2") (pintype "passive"))
      (node (ref "U10") (pin "28") (pinfunction "PB2_28") (pintype "passive"))
    )
    (net (code "3") (name "/CF1") (class "Default")
      (node (ref "U4") (pin "23") (pinfunction "CF1_23") (pintype "passive"))
      (node (ref "U9") (pin "4") (pinfunction "A3_4") (pintype "input"))
    )
    (net (code "4") (name "/CF1_OUT") (class "Default")
      (node (ref "T7") (pin "1") (pinfunction "1_1") (pintype "passive"))
      (node (ref "U10") (pin "26") (pinfunction "PB0_26") (pintype "passive"))
      (node (ref "U9") (pin "13") (pinfunction "B3_13") (pintype "output"))
    )
    (net (code "5") (name "/CF2") (class "Default")
      (node (ref "U4") (pin "24") (pinfunction "CF2_24") (pintype "passive"))
      (node (ref "U9") (pin "3") (pinfunction "A2_3") (pintype "input"))
    )
    (net (code "6") (name "/CF2_OUT") (class "Default")
      (node (ref "T12") (pin "1") (pinfunction "1_1") (pintype "passive"))
      (node (ref "U10") (pin "14") (pinfunction "PA0_14") (pintype "passive"))
      (node (ref "U9") (pin "14") (pinfunction "B2_14") (pintype "output"))
    )
    (net (code "7") (name "/CLK") (class "Default")
      (node (ref "T15") (pin "1") (pinfunction "1_1") (pintype "passive"))
      (node (ref "U10") (pin "29") (pinfunction "PB10_29") (pintype "passive"))
      (node (ref "U5") (pin "5") (pinfunction "SD_CLK_5") (pintype "passive"))
      (node (ref "U7") (pin "5") (pinfunction "CLK_5") (pintype "passive"))
    )
    (net (code "8") (name "/CLK:ADE") (class "Default")
      (node (ref "U4") (pin "25") (pinfunction "SCLK_25") (pintype "passive"))
      (node (ref "U8") (pin "5") (pinfunction "A4_5") (pintype "input"))
    )
    (net (code "9") (name "/CLK:ADE_OUT") (class "Default")
      (node (ref "T5") (pin "1") (pinfunction "1_1") (pintype "passive"))
      (node (ref "U10") (pin "21") (pinfunction "PA5_21") (pintype "passive"))
      (node (ref "U8") (pin "12") (pinfunction "B4_12") (pintype "output"))
    )
    (net (code "10") (name "/DC:LCD") (class "Default")
      (node (ref "U10") (pin "9") (pinfunction "PC1_9") (pintype "passive"))
      (node (ref "U7") (pin "3") (pinfunction "DC_3") (pintype "passive"))
    )
    (net (code "11") (name "/IAN") (class "Default")
      (node (ref "C14") (pin "1") (pintype "passive"))
      (node (ref "R7") (pin "2") (pinfunction "2_2") (pintype "passive"))
      (node (ref "U4") (pin "6") (pinfunction "IAN_6") (pintype "passive"))
    )
    (net (code "12") (name "/IAP") (class "Default")
      (node (ref "C13") (pin "2") (pintype "passive"))
      (node (ref "R3") (pin "2") (pinfunction "2_2") (pintype "passive"))
      (node (ref "U4") (pin "5") (pinfunction "IAP_5") (pintype "passive"))
    )
    (net (code "13") (name "/IBN") (class "Default")
      (node (ref "C19") (pin "1") (pintype "passive"))
      (node (ref "R13") (pin "2") (pinfunction "2_2") (pintype "passive"))
      (node (ref "U4") (pin "10") (pinfunction "IBN_10") (pintype "passive"))
    )
    (net (code "14") (name "/IBP") (class "Default")
      (node (ref "C16") (pin "2") (pintype "passive"))
      (node (ref "R9") (pin "2") (pinfunction "2_2") (pintype "passive"))
      (node (ref "U4") (pin "9") (pinfunction "IBP_9") (pintype "passive"))
    )
    (net (code "15") (name "/IRQ") (class "Default")
      (node (ref "U4") (pin "22") (pinfunction "~{IRQ}_22") (pintype "passive"))
      (node (ref "U9") (pin "5") (pinfunction "A4_5") (pintype "input"))
    )
    (net (code "16") (name "/IRQ_OUT") (class "Default")
      (node (ref "T8") (pin "1") (pinfunction "1_1") (pintype "passive"))
      (node (ref "U10") (pin "27") (pinfunction "PB1_27") (pintype "passive"))
      (node (ref "U9") (pin "12") (pinfunction "B4_12") (pintype "output"))
    )
    (net (code "17") (name "/L") (class "Default")
      (node (ref "F1") (pin "2") (pinfunction "2_2") (pintype "passive"))
      (node (ref "U1") (pin "1") (pinfunction "L_1") (pintype "passive"))
      (node (ref "U6") (pin "1") (pinfunction "L_1") (pintype "passive"))
    )
    (net (code "18") (name "/L2") (class "Default")
      (node (ref "J19") (pin "2") (pinfunction "2_2") (pintype "passive"))
      (node (ref "J20") (pin "2") (pinfunction "2_2") (pintype "passive"))
      (node (ref "J5") (pin "2") (pintype "passive"))
      (node (ref "J6") (pin "2") (pintype "passive"))
      (node (ref "U6") (pin "3") (pinfunction "L-9V_3") (pintype "passive"))
    )
    (net (code "19") (name "/LED1") (class "Default")
      (node (ref "R20") (pin "1") (pinfunction "1_1") (pintype "passive"))
      (node (ref "U10") (pin "39") (pinfunction "PC8_39") (pintype "passive"))
    )
    (net (code "20") (name "/LED2") (class "Default")
      (node (ref "R21") (pin "1") (pinfunction "1_1") (pintype "passive"))
      (node (ref "U10") (pin "40") (pinfunction "PC9_40") (pintype "passive"))
    )
    (net (code "21") (name "/LED3") (class "Default")
      (node (ref "R22") (pin "1") (pinfunction "1_1") (pintype "passive"))
      (node (ref "U10") (pin "41") (pinfunction "PA8_41") (pintype "passive"))
    )
    (net (code "22") (name "/LED4") (class "Default")
      (node (ref "R23") (pin "1") (pinfunction "1_1") (pintype "passive"))
      (node (ref "U10") (pin "44") (pinfunction "PA11_44") (pintype "passive"))
    )
    (net (code "23") (name "/MISO") (class "Default")
      (node (ref "T13") (pin "1") (pinfunction "1_1") (pintype "passive"))
      (node (ref "U10") (pin "10") (pinfunction "PC2_10") (pintype "passive"))
      (node (ref "U5") (pin "7") (pinfunction "SD_DAT0/MISO_7") (pintype "passive"))
      (node (ref "U7") (pin "1") (pinfunction "RST_1") (pintype "passive"))
    )
    (net (code "24") (name "/MISO:ADE") (class "Default")
      (node (ref "R8") (pin "2") (pinfunction "2_2") (pintype "passive"))
      (node (ref "U4") (pin "26") (pinfunction "MISO/SDA/TX_26") (pintype "passive"))
      (node (ref "U8") (pin "4") (pinfunction "A3_4") (pintype "input"))
    )
    (net (code "25") (name "/MISO:ADE_OUT") (class "Default")
      (node (ref "T3") (pin "1") (pinfunction "1_1") (pintype "passive"))
      (node (ref "U10") (pin "22") (pinfunction "PA6_22") (pintype "passive"))
      (node (ref "U10") (pin "43") (pinfunction "PA10_43") (pintype "passive"))
      (node (ref "U8") (pin "13") (pinfunction "B3_13") (pintype "output"))
    )
    (net (code "26") (name "/MOSI") (class "Default")
      (node (ref "T14") (pin "1") (pinfunction "1_1") (pintype "passive"))
      (node (ref "U10") (pin "11") (pinfunction "PC3_11") (pintype "passive"))
      (node (ref "U5") (pin "3") (pinfunction "CMD_3") (pintype "passive"))
      (node (ref "U7") (pin "4") (pinfunction "DIN_4") (pintype "passive"))
    )
    (net (code "27") (name "/MOSI:ADE") (class "Default")
      (node (ref "R6") (pin "2") (pinfunction "2_2") (pintype "passive"))
      (node (ref "U4") (pin "27") (pinfunction "MOSI/SCL/RX_27") (pintype "passive"))
      (node (ref "U8") (pin "3") (pinfunction "A2_3") (pintype "input"))
    )
    (net (code "28") (name "/MOSI:ADE_OUT") (class "Default")
      (node (ref "T4") (pin "1") (pinfunction "1_1") (pintype "passive"))
      (node (ref "U10") (pin "23") (pinfunction "PA7_23") (pintype "passive"))
      (node (ref "U10") (pin "42") (pinfunction "PA9_42") (pintype "passive"))
      (node (ref "U8") (pin "14") (pinfunction "B2_14") (pintype "output"))
    )
    (net (code "29") (name "/N") (class "Default")
      (node (ref "F2") (pin "2") (pinfunction "2_2") (pintype "passive"))
      (node (ref "U1") (pin "2") (pinfunction "N_2") (pintype "passive"))
      (node (ref "U6") (pin "2") (pinfunction "N_2") (pintype "passive"))
    )
    (net (code "30") (name "/REF") (class "Default")
      (node (ref "C5") (pin "1") (pintype "passive"))
      (node (ref "C6") (pin "1") (pintype "passive"))
      (node (ref "U4") (pin "13") (pinfunction "REF_13") (pintype "passive"))
    )
    (net (code "31") (name "/RES:ADE") (class "Default")
      (node (ref "C2") (pin "1") (pintype "passive"))
      (node (ref "R1") (pin "2") (pinfunction "2_2") (pintype "passive"))
      (node (ref "U10") (pin "25") (pinfunction "PC5_25") (pintype "passive"))
      (node (ref "U4") (pin "2") (pinfunction "~{RESET}_2") (pintype "passive"))
    )
    (net (code "32") (name "/RESET") (class "Default")
      (node (ref "C42") (pin "1") (pintype "passive"))
      (node (ref "P1") (pin "10") (pinfunction "nRESET_10") (pintype "passive"))
      (node (ref "S5") (pin "1") (pinfunction "1_1") (pintype "passive"))
      (node (ref "U10") (pin "7") (pinfunction "NRST_7") (pintype "passive"))
    )
    (net (code "33") (name "/REVP") (class "Default")
      (node (ref "U4") (pin "20") (pinfunction "~{REVP}_20") (pintype "passive"))
      (node (ref "U9") (pin "10") (pinfunction "B6_10") (pintype "input"))
    )
    (net (code "34") (name "/REVP_OUT") (class "Default")
      (node (ref "T10") (pin "1") (pinfunction "1_1") (pintype "passive"))
      (node (ref "U10") (pin "36") (pinfunction "PB15_36") (pintype "passive"))
      (node (ref "U9") (pin "7") (pinfunction "A6_7") (pintype "output"))
    )
    (net (code "35") (name "/RST:ESP") (class "Default")
      (node (ref "U10") (pin "15") (pinfunction "PA1_15") (pintype "passive"))
      (node (ref "U2") (pin "13") (pinfunction "RST_13") (pintype "passive"))
    )
    (net (code "36") (name "/RXD:CP") (class "Default")
      (node (ref "T20") (pin "1") (pinfunction "1_1") (pintype "passive"))
      (node (ref "U10") (pin "37") (pinfunction "PC6_37") (pintype "passive"))
      (node (ref "U3") (pin "20") (pinfunction "RXD_20") (pintype "input"))
    )
    (net (code "37") (name "/RXD:ESP") (class "Default")
      (node (ref "T18") (pin "1") (pinfunction "1_1") (pintype "passive"))
      (node (ref "U10") (pin "16") (pinfunction "PA2_16") (pintype "passive"))
      (node (ref "U2") (pin "17") (pinfunction "RXD_17") (pintype "passive"))
    )
    (net (code "38") (name "/SS:ADE") (class "Default")
      (node (ref "U4") (pin "28") (pinfunction "CS_28") (pintype "passive"))
      (node (ref "U8") (pin "2") (pinfunction "A1_2") (pintype "input"))
    )
    (net (code "39") (name "/SS:ADE_OUT") (class "Default")
      (node (ref "T6") (pin "1") (pinfunction "1_1") (pintype "passive"))
      (node (ref "U10") (pin "24") (pinfunction "PC4_24") (pintype "passive"))
      (node (ref "U8") (pin "15") (pinfunction "B1_15") (pintype "output"))
    )
    (net (code "40") (name "/SS:LCD") (class "Default")
      (node (ref "T17") (pin "1") (pinfunction "1_1") (pintype "passive"))
      (node (ref "U10") (pin "8") (pinfunction "PC0_8") (pintype "passive"))
      (node (ref "U7") (pin "2") (pinfunction "CE_2") (pintype "passive"))
    )
    (net (code "41") (name "/SS:SD") (class "Default")
      (node (ref "T16") (pin "1") (pinfunction "1_1") (pintype "passive"))
      (node (ref "U10") (pin "2") (pinfunction "PC13_2") (pintype "passive"))
      (node (ref "U5") (pin "2") (pinfunction "CD/DAT3_2") (pintype "passive"))
    )
    (net (code "42") (name "/SW1") (class "Default")
      (node (ref "C27") (pin "1") (pintype "passive"))
      (node (ref "S1") (pin "1") (pinfunction "1_1") (pintype "passive"))
      (node (ref "U10") (pin "56") (pinfunction "PB4_56") (pintype "passive"))
    )
    (net (code "43") (name "/SW2") (class "Default")
      (node (ref "C34") (pin "1") (pintype "passive"))
      (node (ref "S2") (pin "1") (pinfunction "1_1") (pintype "passive"))
      (node (ref "U10") (pin "57") (pinfunction "PB5_57") (pintype "passive"))
    )
    (net (code "44") (name "/SW3") (class "Default")
      (node (ref "C35") (pin "1") (pintype "passive"))
      (node (ref "S3") (pin "1") (pinfunction "1_1") (pintype "passive"))
      (node (ref "U10") (pin "58") (pinfunction "PB6_58") (pintype "passive"))
    )
    (net (code "45") (name "/SW4") (class "Default")
      (node (ref "C36") (pin "1") (pintype "passive"))
      (node (ref "S4") (pin "1") (pinfunction "1_1") (pintype "passive"))
      (node (ref "U10") (pin "59") (pinfunction "PB7_59") (pintype "passive"))
    )
    (net (code "46") (name "/SWCLK") (class "Default")
      (node (ref "P1") (pin "4") (pinfunction "SWCLK_4") (pintype "passive"))
      (node (ref "U10") (pin "35") (pinfunction "PB14_35") (pintype "passive"))
    )
    (net (code "47") (name "/SWDIO") (class "Default")
      (node (ref "P1") (pin "2") (pinfunction "SWDIO_2") (pintype "passive"))
      (node (ref "U10") (pin "34") (pinfunction "PB13_34") (pintype "passive"))
    )
    (net (code "48") (name "/SWO") (class "Default")
      (node (ref "P1") (pin "6") (pinfunction "SWO_6") (pintype "passive"))
      (node (ref "U10") (pin "55") (pinfunction "PB3_55") (pintype "passive"))
    )
    (net (code "49") (name "/TXD:CP") (class "Default")
      (node (ref "T21") (pin "1") (pinfunction "1_1") (pintype "passive"))
      (node (ref "U10") (pin "38") (pinfunction "PC7_38") (pintype "passive"))
      (node (ref "U3") (pin "21") (pinfunction "TXD_21") (pintype "output"))
    )
    (net (code "50") (name "/TXD:ESP") (class "Default")
      (node (ref "T19") (pin "1") (pinfunction "1_1") (pintype "passive"))
      (node (ref "U10") (pin "17") (pinfunction "PA3_17") (pintype "passive"))
      (node (ref "U2") (pin "16") (pinfunction "TXD_16") (pintype "passive"))
    )
    (net (code "51") (name "/VINTA") (class "Default")
      (node (ref "C7") (pin "1") (pintype "passive"))
      (node (ref "C8") (pin "1") (pintype "passive"))
      (node (ref "U4") (pin "15") (pinfunction "VINTA_15") (pintype "passive"))
    )
    (net (code "52") (name "/VINTD") (class "Default")
      (node (ref "C10") (pin "1") (pintype "passive"))
      (node (ref "C9") (pin "1") (pintype "passive"))
      (node (ref "U4") (pin "3") (pinfunction "VINTD_3") (pintype "passive"))
    )
    (net (code "53") (name "/VN") (class "Default")
      (node (ref "C24") (pin "2") (pintype "passive"))
      (node (ref "R19") (pin "1") (pinfunction "1_1") (pintype "passive"))
      (node (ref "U4") (pin "11") (pinfunction "VN_11") (pintype "passive"))
    )
    (net (code "54") (name "/VP") (class "Default")
      (node (ref "C22") (pin "2") (pintype "passive"))
      (node (ref "C23") (pin "2") (pintype "passive"))
      (node (ref "R14") (pin "2") (pinfunction "2_2") (pintype "passive"))
      (node (ref "R16") (pin "1") (pinfunction "1_1") (pintype "passive"))
      (node (ref "R17") (pin "1") (pinfunction "1_1") (pintype "passive"))
      (node (ref "R18") (pin "1") (pinfunction "1_1") (pintype "passive"))
      (node (ref "U4") (pin "12") (pinfunction "VP_12") (pintype "passive"))
    )
    (net (code "55") (name "/XT1") (class "Default")
      (node (ref "C25") (pin "1") (pintype "passive"))
      (node (ref "U10") (pin "5") (pinfunction "PH0_5") (pintype "passive"))
      (node (ref "XT2") (pin "2") (pinfunction "OUT_2") (pintype "passive"))
    )
    (net (code "56") (name "/XT2") (class "Default")
      (node (ref "C28") (pin "1") (pintype "passive"))
      (node (ref "U10") (pin "6") (pinfunction "PH1_6") (pintype "passive"))
      (node (ref "XT2") (pin "1") (pinfunction "IN_1") (pintype "passive"))
    )
    (net (code "57") (name "/XT2_1") (class "Default")
      (node (ref "C26") (pin "1") (pintype "passive"))
      (node (ref "U10") (pin "3") (pinfunction "PC14_3") (pintype "passive"))
      (node (ref "XT3") (pin "2") (pinfunction "OUT_2") (pintype "passive"))
    )
    (net (code "58") (name "/XT2_2") (class "Default")
      (node (ref "C29") (pin "1") (pintype "passive"))
      (node (ref "U10") (pin "4") (pinfunction "PC15_4") (pintype "passive"))
      (node (ref "XT3") (pin "1") (pinfunction "IN_1") (pintype "passive"))
    )
    (net (code "59") (name "/ZX") (class "Default")
      (node (ref "U4") (pin "1") (pinfunction "ZX_1") (pintype "passive"))
      (node (ref "U9") (pin "2") (pinfunction "A1_2") (pintype "input"))
    )
    (net (code "60") (name "/ZX1") (class "Default")
      (node (ref "U4") (pin "21") (pinfunction "ZX_I_21") (pintype "passive"))
      (node (ref "U9") (pin "11") (pinfunction "B5_11") (pintype "input"))
    )
    (net (code "61") (name "/ZX1_OUT") (class "Default")
      (node (ref "T11") (pin "1") (pinfunction "1_1") (pintype "passive"))
      (node (ref "U10") (pin "33") (pinfunction "PB12_33") (pintype "passive"))
      (node (ref "U9") (pin "6") (pinfunction "A5_6") (pintype "output"))
    )
    (net (code "62") (name "/ZX_OUT") (class "Default")
      (node (ref "T9") (pin "1") (pinfunction "1_1") (pintype "passive"))
      (node (ref "U10") (pin "20") (pinfunction "PA4_20") (pintype "passive"))
      (node (ref "U9") (pin "15") (pinfunction "B1_15") (pintype "output"))
    )
    (net (code "63") (name "GND") (class "Default")
      (node (ref "C1") (pin "1") (pintype "passive"))
      (node (ref "C10") (pin "2") (pintype "passive"))
      (node (ref "C11") (pin "1") (pintype "passive"))
      (node (ref "C12") (pin "2") (pintype "passive"))
      (node (ref "C13") (pin "1") (pintype "passive"))
      (node (ref "C14") (pin "2") (pintype "passive"))
      (node (ref "C15") (pin "2") (pintype "passive"))
      (node (ref "C16") (pin "1") (pintype "passive"))
      (node (ref "C17") (pin "1") (pintype "passive"))
      (node (ref "C18") (pin "1") (pintype "passive"))
      (node (ref "C19") (pin "2") (pintype "passive"))
      (node (ref "C20") (pin "1") (pintype "passive"))
      (node (ref "C21") (pin "1") (pintype "passive"))
      (node (ref "C22") (pin "1") (pintype "passive"))
      (node (ref "C23") (pin "1") (pintype "passive"))
      (node (ref "C24") (pin "1") (pintype "passive"))
      (node (ref "C25") (pin "2") (pintype "passive"))
      (node (ref "C26") (pin "2") (pintype "passive"))
      (node (ref "C27") (pin "2") (pintype "passive"))
      (node (ref "C28") (pin "2") (pintype "passive"))
      (node (ref "C29") (pin "2") (pintype "passive"))
      (node (ref "C3") (pin "2") (pintype "passive"))
      (node (ref "C30") (pin "2") (pintype "passive"))
      (node (ref "C31") (pin "2") (pintype "passive"))
      (node (ref "C32") (pin "2") (pintype "passive"))
      (node (ref "C33") (pin "2") (pintype "passive"))
      (node (ref "C34") (pin "2") (pintype "passive"))
      (node (ref "C35") (pin "2") (pintype "passive"))
      (node (ref "C36") (pin "2") (pintype "passive"))
      (node (ref "C37") (pin "2") (pintype "passive"))
      (node (ref "C38") (pin "2") (pintype "passive"))
      (node (ref "C39") (pin "2") (pintype "passive"))
      (node (ref "C4") (pin "2") (pintype "passive"))
      (node (ref "C40") (pin "2") (pintype "passive"))
      (node (ref "C41") (pin "2") (pintype "passive"))
      (node (ref "C42") (pin "2") (pintype "passive"))
      (node (ref "C43") (pin "2") (pintype "passive"))
      (node (ref "C44") (pin "2") (pintype "passive"))
      (node (ref "C45") (pin "2") (pintype "passive"))
      (node (ref "C46") (pin "2") (pintype "passive"))
      (node (ref "C47") (pin "1") (pintype "passive"))
      (node (ref "C5") (pin "2") (pintype "passive"))
      (node (ref "C6") (pin "2") (pintype "passive"))
      (node (ref "C7") (pin "2") (pintype "passive"))
      (node (ref "C8") (pin "2") (pintype "passive"))
      (node (ref "C9") (pin "2") (pintype "passive"))
      (node (ref "J16") (pin "2") (pintype "passive"))
      (node (ref "J17") (pin "2") (pintype "passive"))
      (node (ref "J19") (pin "1") (pinfunction "1_1") (pintype "passive"))
      (node (ref "J2") (pin "2") (pintype "passive"))
      (node (ref "J20") (pin "1") (pinfunction "1_1") (pintype "passive"))
      (node (ref "J23") (pin "2") (pinfunction "2_2") (pintype "passive"))
      (node (ref "J24") (pin "2") (pinfunction "2_2") (pintype "passive"))
      (node (ref "J3") (pin "2") (pintype "passive"))
      (node (ref "J4") (pin "5") (pinfunction "GND_5") (pintype "passive"))
      (node (ref "LED1") (pin "K") (pinfunction "K_K") (pintype "passive"))
      (node (ref "LED2") (pin "K") (pinfunction "K_K") (pintype "passive"))
      (node (ref "LED3") (pin "K") (pinfunction "K_K") (pintype "passive"))
      (node (ref "LED4") (pin "K") (pinfunction "K_K") (pintype "passive"))
      (node (ref "P1") (pin "3") (pinfunction "GND_3") (pintype "passive"))
      (node (ref "P1") (pin "5") (pinfunction "GND_5") (pintype "passive"))
      (node (ref "R11") (pin "2") (pinfunction "2_2") (pintype "passive"))
      (node (ref "R12") (pin "1") (pinfunction "1_1") (pintype "passive"))
      (node (ref "R17") (pin "2") (pinfunction "2_2") (pintype "passive"))
      (node (ref "R18") (pin "2") (pinfunction "2_2") (pintype "passive"))
      (node (ref "R19") (pin "2") (pinfunction "2_2") (pintype "passive"))
      (node (ref "R4") (pin "2") (pinfunction "2_2") (pintype "passive"))
      (node (ref "R5") (pin "1") (pinfunction "1_1") (pintype "passive"))
      (node (ref "S1") (pin "2") (pinfunction "2_2") (pintype "passive"))
      (node (ref "S2") (pin "2") (pinfunction "2_2") (pintype "passive"))
      (node (ref "S3") (pin "2") (pinfunction "2_2") (pintype "passive"))
      (node (ref "S4") (pin "2") (pinfunction "2_2") (pintype "passive"))
      (node (ref "S5") (pin "2") (pinfunction "2_2") (pintype "passive"))
      (node (ref "U1") (pin "3") (pinfunction "GND_3") (pintype "passive"))
      (node (ref "U10") (pin "12") (pinfunction "VSSA/VREF-_12") (pintype "passive"))
      (node (ref "U10") (pin "18") (pinfunction "VSS_18") (pintype "passive"))
      (node (ref "U10") (pin "31") (pinfunction "VSS_31") (pintype "passive"))
      (node (ref "U10") (pin "47") (pinfunction "VSS_47") (pintype "passive"))
      (node (ref "U10") (pin "63") (pinfunction "VSS_63") (pintype "passive"))
      (node (ref "U2") (pin "10") (pinfunction "GND_10") (pintype "passive"))
      (node (ref "U2") (pin "15") (pinfunction "GND_15") (pintype "passive"))
      (node (ref "U2") (pin "19") (pinfunction "GND_19") (pintype "passive"))
      (node (ref "U2") (pin "9") (pinfunction "GND_9") (pintype "passive"))
      (node (ref "U3") (pin "2") (pinfunction "GND_2") (pintype "power_in"))
      (node (ref "U3") (pin "25") (pinfunction "GND_25") (pintype "power_in"))
      (node (ref "U4") (pin "14") (pinfunction "P_LOW_14") (pintype "passive"))
      (node (ref "U4") (pin "16") (pinfunction "AGND_16") (pintype "passive"))
      (node (ref "U4") (pin "4") (pinfunction "DGND_4") (pintype "passive"))
      (node (ref "U5") (pin "10") (pinfunction "GND_10") (pintype "passive"))
      (node (ref "U5") (pin "11") (pinfunction "GND_11") (pintype "passive"))
      (node (ref "U5") (pin "12") (pinfunction "GND_12") (pintype "passive"))
      (node (ref "U5") (pin "6") (pinfunction "GND_6") (pintype "passive"))
      (node (ref "U5") (pin "9") (pinfunction "GND_9") (pintype "passive"))
      (node (ref "U6") (pin "4") (pinfunction "N-9V_4") (pintype "passive"))
      (node (ref "U7") (pin "8") (pinfunction "GND_8") (pintype "passive"))
      (node (ref "U8") (pin "8") (pinfunction "GND1_8") (pintype "power_in"))
      (node (ref "U8") (pin "9") (pinfunction "GND2_9") (pintype "power_in"))
      (node (ref "U9") (pin "8") (pinfunction "GND1_8") (pintype "power_in"))
      (node (ref "U9") (pin "9") (pinfunction "GND2_9") (pintype "power_in"))
    )
    (net (code "64") (name "Net-(F1-Pad1)") (class "Default")
      (node (ref "F1") (pin "1") (pinfunction "1_1") (pintype "passive"))
      (node (ref "J1") (pin "1") (pinfunction "1_1") (pintype "passive"))
    )
    (net (code "65") (name "Net-(F2-Pad1)") (class "Default")
      (node (ref "F2") (pin "1") (pinfunction "1_1") (pintype "passive"))
      (node (ref "J1") (pin "2") (pinfunction "2_2") (pintype "passive"))
    )
    (net (code "66") (name "Net-(J4-D+)") (class "Default")
      (node (ref "J4") (pin "3") (pinfunction "D+_3") (pintype "passive"))
      (node (ref "U3") (pin "3") (pinfunction "D+_3") (pintype "bidirectional"))
    )
    (net (code "67") (name "Net-(J4-D-)") (class "Default")
      (node (ref "J4") (pin "2") (pinfunction "D-_2") (pintype "passive"))
      (node (ref "U3") (pin "4") (pinfunction "D-_4") (pintype "bidirectional"))
    )
    (net (code "68") (name "Net-(J4-VBUS)") (class "Default")
      (node (ref "C18") (pin "2") (pintype "passive"))
      (node (ref "J4") (pin "1") (pinfunction "VBUS_1") (pintype "passive"))
      (node (ref "U3") (pin "7") (pinfunction "REGIN_7") (pintype "power_in"))
      (node (ref "U3") (pin "8") (pinfunction "VBUS_8") (pintype "input"))
    )
    (net (code "69") (name "Net-(J5-Pad1)") (class "Default")
      (node (ref "J5") (pin "1") (pintype "passive"))
      (node (ref "R14") (pin "1") (pinfunction "1_1") (pintype "passive"))
    )
    (net (code "70") (name "Net-(J6-Pad1)") (class "Default")
      (node (ref "J6") (pin "1") (pintype "passive"))
      (node (ref "R15") (pin "2") (pinfunction "2_2") (pintype "passive"))
    )
    (net (code "71") (name "Net-(J13-Pad2)") (class "Default")
      (node (ref "J13") (pin "2") (pintype "passive"))
      (node (ref "J16") (pin "1") (pintype "passive"))
      (node (ref "R24") (pin "1") (pinfunction "1_1") (pintype "passive"))
    )
    (net (code "72") (name "Net-(J14-Pad2)") (class "Default")
      (node (ref "J14") (pin "2") (pintype "passive"))
      (node (ref "J17") (pin "1") (pintype "passive"))
      (node (ref "R25") (pin "1") (pinfunction "1_1") (pintype "passive"))
    )
    (net (code "73") (name "Net-(LED1-PadA)") (class "Default")
      (node (ref "LED1") (pin "A") (pinfunction "A_A") (pintype "passive"))
      (node (ref "R20") (pin "2") (pinfunction "2_2") (pintype "passive"))
    )
    (net (code "74") (name "Net-(LED2-PadA)") (class "Default")
      (node (ref "LED2") (pin "A") (pinfunction "A_A") (pintype "passive"))
      (node (ref "R21") (pin "2") (pinfunction "2_2") (pintype "passive"))
    )
    (net (code "75") (name "Net-(LED3-PadA)") (class "Default")
      (node (ref "LED3") (pin "A") (pinfunction "A_A") (pintype "passive"))
      (node (ref "R22") (pin "2") (pinfunction "2_2") (pintype "passive"))
    )
    (net (code "76") (name "Net-(LED4-PadA)") (class "Default")
      (node (ref "LED4") (pin "A") (pinfunction "A_A") (pintype "passive"))
      (node (ref "R23") (pin "2") (pinfunction "2_2") (pintype "passive"))
    )
    (net (code "77") (name "Net-(R15-Pad1)") (class "Default")
      (node (ref "R15") (pin "1") (pinfunction "1_1") (pintype "passive"))
      (node (ref "R16") (pin "2") (pinfunction "2_2") (pintype "passive"))
    )
    (net (code "78") (name "Net-(T1-21)") (class "Default")
      (node (ref "R3") (pin "1") (pinfunction "1_1") (pintype "passive"))
      (node (ref "R4") (pin "1") (pinfunction "1_1") (pintype "passive"))
      (node (ref "T1") (pin "1") (pinfunction "21_1") (pintype "passive"))
    )
    (net (code "79") (name "Net-(T1-22)") (class "Default")
      (node (ref "R5") (pin "2") (pinfunction "2_2") (pintype "passive"))
      (node (ref "R7") (pin "1") (pinfunction "1_1") (pintype "passive"))
      (node (ref "T1") (pin "2") (pinfunction "22_2") (pintype "passive"))
    )
    (net (code "80") (name "Net-(T2-21)") (class "Default")
      (node (ref "R11") (pin "1") (pinfunction "1_1") (pintype "passive"))
      (node (ref "R9") (pin "1") (pinfunction "1_1") (pintype "passive"))
      (node (ref "T2") (pin "1") (pinfunction "21_1") (pintype "passive"))
    )
    (net (code "81") (name "Net-(T2-22)") (class "Default")
      (node (ref "R12") (pin "2") (pinfunction "2_2") (pintype "passive"))
      (node (ref "R13") (pin "1") (pinfunction "1_1") (pintype "passive"))
      (node (ref "T2") (pin "2") (pinfunction "22_2") (pintype "passive"))
    )
    (net (code "82") (name "Net-(U2-EN)") (class "Default")
      (node (ref "C12") (pin "1") (pintype "passive"))
      (node (ref "R2") (pin "1") (pinfunction "1_1") (pintype "passive"))
      (node (ref "U2") (pin "2") (pinfunction "EN_2") (pintype "passive"))
    )
    (net (code "83") (name "Net-(U2-IO0)") (class "Default")
      (node (ref "J3") (pin "1") (pintype "passive"))
      (node (ref "U2") (pin "8") (pinfunction "IO0_8") (pintype "passive"))
    )
    (net (code "84") (name "Net-(U2-IO15)") (class "Default")
      (node (ref "J2") (pin "1") (pintype "passive"))
      (node (ref "U2") (pin "6") (pinfunction "IO15_6") (pintype "passive"))
    )
    (net (code "85") (name "Net-(U3-VDD)") (class "Default")
      (node (ref "C20") (pin "2") (pintype "passive"))
      (node (ref "R10") (pin "1") (pinfunction "1_1") (pintype "passive"))
      (node (ref "U3") (pin "5") (pinfunction "VIO_5") (pintype "power_in"))
      (node (ref "U3") (pin "6") (pinfunction "VDD_6") (pintype "power_in"))
    )
    (net (code "86") (name "Net-(U3-VPP)") (class "Default")
      (node (ref "C15") (pin "1") (pintype "passive"))
      (node (ref "U3") (pin "16") (pinfunction "VPP_16") (pintype "passive"))
    )
    (net (code "87") (name "Net-(U3-~{RST})") (class "Default")
      (node (ref "R10") (pin "2") (pinfunction "2_2") (pintype "passive"))
      (node (ref "U3") (pin "9") (pinfunction "~{RST}_9") (pintype "bidirectional"))
    )
    (net (code "88") (name "Net-(U4-CLKIN)") (class "Default")
      (node (ref "C21") (pin "2") (pintype "passive"))
      (node (ref "U4") (pin "18") (pinfunction "CLKIN_18") (pintype "passive"))
      (node (ref "XT1") (pin "1") (pinfunction "IN_1") (pintype "passive"))
    )
    (net (code "89") (name "Net-(U4-CLK_OUT)") (class "Default")
      (node (ref "C17") (pin "2") (pintype "passive"))
      (node (ref "U4") (pin "19") (pinfunction "CLK_OUT_19") (pintype "passive"))
      (node (ref "XT1") (pin "2") (pinfunction "OUT_2") (pintype "passive"))
    )
    (net (code "90") (name "Net-(U10-VCAP_1)") (class "Default")
      (node (ref "C47") (pin "2") (pintype "passive"))
      (node (ref "U10") (pin "30") (pinfunction "VCAP_1_30") (pintype "passive"))
    )
    (net (code "91") (name "VCC") (class "Default")
      (node (ref "C1") (pin "2") (pintype "passive"))
      (node (ref "C11") (pin "2") (pintype "passive"))
      (node (ref "C2") (pin "2") (pintype "passive"))
      (node (ref "C3") (pin "1") (pintype "passive"))
      (node (ref "C30") (pin "1") (pintype "passive"))
      (node (ref "C31") (pin "1") (pintype "passive"))
      (node (ref "C32") (pin "1") (pintype "passive"))
      (node (ref "C33") (pin "1") (pintype "passive"))
      (node (ref "C37") (pin "1") (pintype "passive"))
      (node (ref "C38") (pin "1") (pintype "passive"))
      (node (ref "C39") (pin "1") (pintype "passive"))
      (node (ref "C4") (pin "1") (pintype "passive"))
      (node (ref "C40") (pin "1") (pintype "passive"))
      (node (ref "C41") (pin "1") (pintype "passive"))
      (node (ref "C43") (pin "1") (pintype "passive"))
      (node (ref "C44") (pin "1") (pintype "passive"))
      (node (ref "C45") (pin "1") (pintype "passive"))
      (node (ref "C46") (pin "1") (pintype "passive"))
      (node (ref "J13") (pin "1") (pintype "passive"))
      (node (ref "J14") (pin "1") (pintype "passive"))
      (node (ref "J23") (pin "1") (pinfunction "1_1") (pintype "passive"))
      (node (ref "J24") (pin "1") (pinfunction "1_1") (pintype "passive"))
      (node (ref "P1") (pin "1") (pinfunction "VTREF_1") (pintype "passive"))
      (node (ref "R1") (pin "1") (pinfunction "1_1") (pintype "passive"))
      (node (ref "R2") (pin "2") (pinfunction "2_2") (pintype "passive"))
      (node (ref "R6") (pin "1") (pinfunction "1_1") (pintype "passive"))
      (node (ref "R8") (pin "1") (pinfunction "1_1") (pintype "passive"))
      (node (ref "U1") (pin "4") (pinfunction "3.3V_4") (pintype "passive"))
      (node (ref "U10") (pin "1") (pinfunction "VBAT_1") (pintype "passive"))
      (node (ref "U10") (pin "13") (pinfunction "VDDA/VREF+_13") (pintype "passive"))
      (node (ref "U10") (pin "19") (pinfunction "VDD_19") (pintype "passive"))
      (node (ref "U10") (pin "32") (pinfunction "VDD_32") (pintype "passive"))
      (node (ref "U10") (pin "48") (pinfunction "VDD_48") (pintype "passive"))
      (node (ref "U10") (pin "64") (pinfunction "VDD_64") (pintype "passive"))
      (node (ref "U2") (pin "1") (pinfunction "3V3_1") (pintype "passive"))
      (node (ref "U4") (pin "17") (pinfunction "VDD_17") (pintype "passive"))
      (node (ref "U4") (pin "7") (pinfunction "P_HIGH_7") (pintype "passive"))
      (node (ref "U4") (pin "8") (pinfunction "P_HIGH_8") (pintype "passive"))
      (node (ref "U5") (pin "4") (pinfunction "VDD_4") (pintype "passive"))
      (node (ref "U7") (pin "6") (pinfunction "VCC_6") (pintype "passive"))
      (node (ref "U8") (pin "1") (pinfunction "VDD1_1") (pintype "power_in"))
      (node (ref "U8") (pin "16") (pinfunction "VDD2_16") (pintype "power_in"))
      (node (ref "U9") (pin "1") (pinfunction "VDD1_1") (pintype "power_in"))
      (node (ref "U9") (pin "16") (pinfunction "VDD2_16") (pintype "power_in"))
    )
    (net (code "92") (name "unconnected-(J4-ID-Pad4)") (class "Default")
      (node (ref "J4") (pin "4") (pinfunction "ID_4") (pintype "passive"))
    )
    (net (code "93") (name "unconnected-(J4-Shell-PadSH)") (class "Default")
      (node (ref "J4") (pin "SH") (pinfunction "Shell_SH") (pintype "passive"))
    )
    (net (code "94") (name "unconnected-(P1-NC-Pad7)") (class "Default")
      (node (ref "P1") (pin "7") (pinfunction "NC_7") (pintype "passive"))
    )
    (net (code "95") (name "unconnected-(P1-NC-Pad8)") (class "Default")
      (node (ref "P1") (pin "8") (pinfunction "NC_8") (pintype "passive"))
    )
    (net (code "96") (name "unconnected-(P1-NC-Pad9)") (class "Default")
      (node (ref "P1") (pin "9") (pinfunction "NC_9") (pintype "passive"))
    )
    (net (code "97") (name "unconnected-(U2-1O2-Pad7)") (class "Default")
      (node (ref "U2") (pin "7") (pinfunction "1O2_7") (pintype "passive"))
    )
    (net (code "98") (name "unconnected-(U2-IO4-Pad18)") (class "Default")
      (node (ref "U2") (pin "18") (pinfunction "IO4_18") (pintype "passive"))
    )
    (net (code "99") (name "unconnected-(U2-IO5-Pad14)") (class "Default")
      (node (ref "U2") (pin "14") (pinfunction "IO5_14") (pintype "passive"))
    )
    (net (code "100") (name "unconnected-(U2-IO12-Pad4)") (class "Default")
      (node (ref "U2") (pin "4") (pinfunction "IO12_4") (pintype "passive"))
    )
    (net (code "101") (name "unconnected-(U2-IO13-Pad5)") (class "Default")
      (node (ref "U2") (pin "5") (pinfunction "IO13_5") (pintype "passive"))
    )
    (net (code "102") (name "unconnected-(U2-IO14-Pad3)") (class "Default")
      (node (ref "U2") (pin "3") (pinfunction "IO14_3") (pintype "passive"))
    )
    (net (code "103") (name "unconnected-(U2-IO16-Pad11)") (class "Default")
      (node (ref "U2") (pin "11") (pinfunction "IO16_11") (pintype "passive"))
    )
    (net (code "104") (name "unconnected-(U2-TOUT-Pad12)") (class "Default")
      (node (ref "U2") (pin "12") (pinfunction "TOUT_12") (pintype "passive"))
    )
    (net (code "105") (name "unconnected-(U3-GPIO.0-Pad14)") (class "Default")
      (node (ref "U3") (pin "14") (pinfunction "GPIO.0_14") (pintype "bidirectional"))
    )
    (net (code "106") (name "unconnected-(U3-GPIO.1-Pad13)") (class "Default")
      (node (ref "U3") (pin "13") (pinfunction "GPIO.1_13") (pintype "bidirectional"))
    )
    (net (code "107") (name "unconnected-(U3-GPIO.2-Pad12)") (class "Default")
      (node (ref "U3") (pin "12") (pinfunction "GPIO.2_12") (pintype "bidirectional"))
    )
    (net (code "108") (name "unconnected-(U3-GPIO.3-Pad11)") (class "Default")
      (node (ref "U3") (pin "11") (pinfunction "GPIO.3_11") (pintype "bidirectional"))
    )
    (net (code "109") (name "unconnected-(U3-NC-Pad10)") (class "Default")
      (node (ref "U3") (pin "10") (pinfunction "NC_10") (pintype "passive"))
    )
    (net (code "110") (name "unconnected-(U3-SUSPEND-Pad17)") (class "Default")
      (node (ref "U3") (pin "17") (pinfunction "SUSPEND_17") (pintype "output"))
    )
    (net (code "111") (name "unconnected-(U3-~{CTS}-Pad18)") (class "Default")
      (node (ref "U3") (pin "18") (pinfunction "~{CTS}_18") (pintype "input"))
    )
    (net (code "112") (name "unconnected-(U3-~{DCD}-Pad24)") (class "Default")
      (node (ref "U3") (pin "24") (pinfunction "~{DCD}_24") (pintype "input"))
    )
    (net (code "113") (name "unconnected-(U3-~{DSR}-Pad22)") (class "Default")
      (node (ref "U3") (pin "22") (pinfunction "~{DSR}_22") (pintype "input"))
    )
    (net (code "114") (name "unconnected-(U3-~{DTR}-Pad23)") (class "Default")
      (node (ref "U3") (pin "23") (pinfunction "~{DTR}_23") (pintype "output"))
    )
    (net (code "115") (name "unconnected-(U3-~{RI}-Pad1)") (class "Default")
      (node (ref "U3") (pin "1") (pinfunction "~{RI}_1") (pintype "input"))
    )
    (net (code "116") (name "unconnected-(U3-~{RTS}-Pad19)") (class "Default")
      (node (ref "U3") (pin "19") (pinfunction "~{RTS}_19") (pintype "output"))
    )
    (net (code "117") (name "unconnected-(U3-~{SUSPEND}-Pad15)") (class "Default")
      (node (ref "U3") (pin "15") (pinfunction "~{SUSPEND}_15") (pintype "output"))
    )
    (net (code "118") (name "unconnected-(U5-SD_DAT1-Pad8)") (class "Default")
      (node (ref "U5") (pin "8") (pinfunction "SD_DAT1_8") (pintype "passive"))
    )
    (net (code "119") (name "unconnected-(U5-SD_DAT2-Pad1)") (class "Default")
      (node (ref "U5") (pin "1") (pinfunction "SD_DAT2_1") (pintype "passive"))
    )
    (net (code "120") (name "unconnected-(U7-LIG-Pad7)") (class "Default")
      (node (ref "U7") (pin "7") (pinfunction "LIG_7") (pintype "passive"))
    )
    (net (code "121") (name "unconnected-(U8-A5-Pad6)") (class "Default")
      (node (ref "U8") (pin "6") (pinfunction "A5_6") (pintype "output"))
    )
    (net (code "122") (name "unconnected-(U8-A6-Pad7)") (class "Default")
      (node (ref "U8") (pin "7") (pinfunction "A6_7") (pintype "output"))
    )
    (net (code "123") (name "unconnected-(U8-B5-Pad11)") (class "Default")
      (node (ref "U8") (pin "11") (pinfunction "B5_11") (pintype "input"))
    )
    (net (code "124") (name "unconnected-(U8-B6-Pad10)") (class "Default")
      (node (ref "U8") (pin "10") (pinfunction "B6_10") (pintype "input"))
    )
    (net (code "125") (name "unconnected-(U10-PA12-Pad45)") (class "Default")
      (node (ref "U10") (pin "45") (pinfunction "PA12_45") (pintype "passive"))
    )
    (net (code "126") (name "unconnected-(U10-PA13-Pad46)") (class "Default")
      (node (ref "U10") (pin "46") (pinfunction "PA13_46") (pintype "passive"))
    )
    (net (code "127") (name "unconnected-(U10-PA14-Pad49)") (class "Default")
      (node (ref "U10") (pin "49") (pinfunction "PA14_49") (pintype "passive"))
    )
    (net (code "128") (name "unconnected-(U10-PA15-Pad50)") (class "Default")
      (node (ref "U10") (pin "50") (pinfunction "PA15_50") (pintype "passive"))
    )
    (net (code "129") (name "unconnected-(U10-PB8-Pad61)") (class "Default")
      (node (ref "U10") (pin "61") (pinfunction "PB8_61") (pintype "passive"))
    )
    (net (code "130") (name "unconnected-(U10-PB9-Pad62)") (class "Default")
      (node (ref "U10") (pin "62") (pinfunction "PB9_62") (pintype "passive"))
    )
    (net (code "131") (name "unconnected-(U10-PB11-Pad54)") (class "Default")
      (node (ref "U10") (pin "54") (pinfunction "PB11_54") (pintype "passive"))
    )
    (net (code "132") (name "unconnected-(U10-PC10-Pad51)") (class "Default")
      (node (ref "U10") (pin "51") (pinfunction "PC10_51") (pintype "passive"))
    )
    (net (code "133") (name "unconnected-(U10-PC11-Pad52)") (class "Default")
      (node (ref "U10") (pin "52") (pinfunction "PC11_52") (pintype "passive"))
    )
    (net (code "134") (name "unconnected-(U10-PC12-Pad53)") (class "Default")
      (node (ref "U10") (pin "53") (pinfunction "PC12_53") (pintype "passive"))
    )
  )
)
